# ProProject__3_0___2023-10-16.net
KiCad netlist of a schematic drawn in EasyEDA Pro
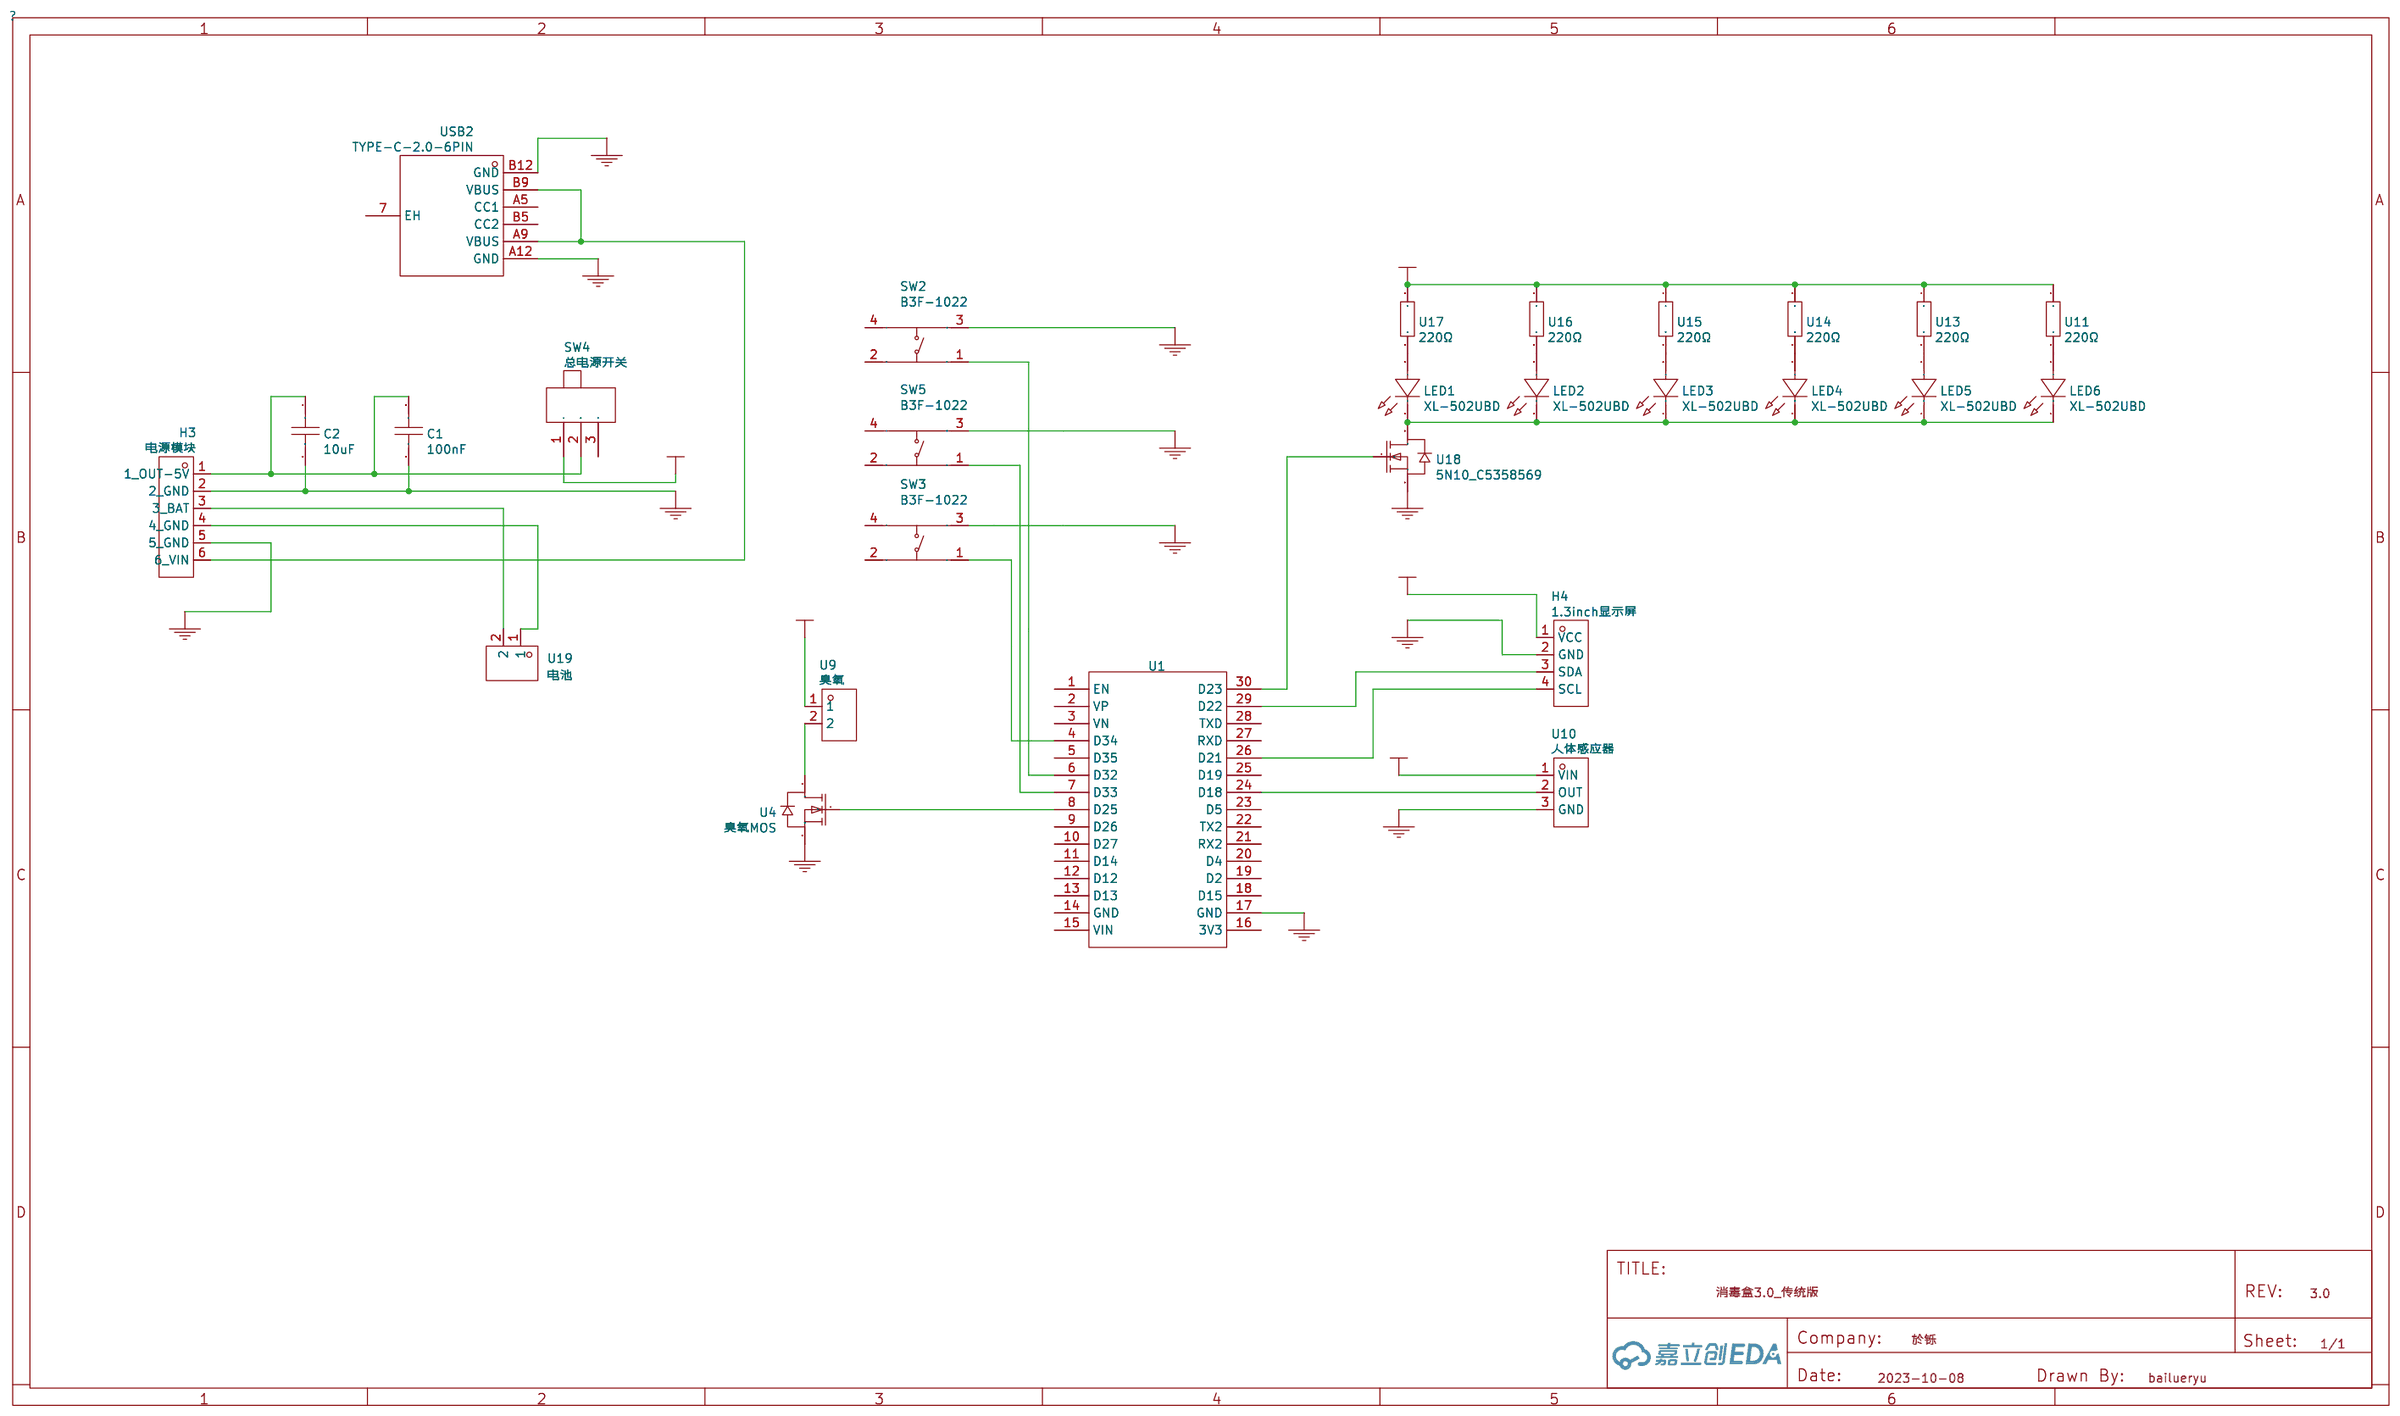
[diagram p0: schematic sheet]

(export (version "E")
  (design (tool "Eeschema 10.0.6"))
  (components
    (comp (ref "C1")
      (value "100nF")
      (footprint "easyedapro:C0603")
      (fields
        (field (name "Manufacturer Part") "MC0603B104K500N8RH")
        (field (name "Manufacturer") "Sunway(信维通信)")
      )
      (libsource (lib "easyedapro") (part "100nF"))
    )
    (comp (ref "C2")
      (value "10uF")
      (footprint "easyedapro:C0603")
      (fields (field (name "Manufacturer") "SAMSUNG(三星)"))
      (libsource (lib "easyedapro") (part "10uF"))
    )
    (comp (ref "H3")
      (value "电源模块")
      (footprint "easyedapro:HDR-TH_6P-P2.54-V-M")
      (fields (field (name "Manufacturer Part") "PZ254V-11-06P") (field (name "Manufacturer") "XFCN(兴飞)"))
      (libsource (lib "easyedapro") (part "电源模块"))
    )
    (comp (ref "H4")
      (value "1.3inch显示屏")
      (footprint "easyedapro:HDR-TH_4P-P2.54-V-M")
      (fields
        (field (name "Manufacturer Part") "KH-2.54PH180-1X4P-L11.5")
        (field (name "Manufacturer") "kinghelm(金航标)")
      )
      (libsource (lib "easyedapro") (part "1.3inch显示屏"))
    )
    (comp (ref "LED1")
      (value "XL-502UBD")
      (footprint "easyedapro:LED-TH_BD5.9-P2.54-RD_BLUE")
      (fields (field (name "Manufacturer") "XINGLIGHT(成兴光)"))
      (libsource (lib "easyedapro") (part "XL-502UBD"))
    )
    (comp (ref "LED2")
      (value "XL-502UBD")
      (footprint "easyedapro:LED-TH_BD5.9-P2.54-RD_BLUE")
      (fields (field (name "Manufacturer") "XINGLIGHT(成兴光)"))
      (libsource (lib "easyedapro") (part "XL-502UBD"))
    )
    (comp (ref "LED3")
      (value "XL-502UBD")
      (footprint "easyedapro:LED-TH_BD5.9-P2.54-RD_BLUE")
      (fields (field (name "Manufacturer") "XINGLIGHT(成兴光)"))
      (libsource (lib "easyedapro") (part "XL-502UBD"))
    )
    (comp (ref "LED4")
      (value "XL-502UBD")
      (footprint "easyedapro:LED-TH_BD5.9-P2.54-RD_BLUE")
      (fields (field (name "Manufacturer") "XINGLIGHT(成兴光)"))
      (libsource (lib "easyedapro") (part "XL-502UBD"))
    )
    (comp (ref "LED5")
      (value "XL-502UBD")
      (footprint "easyedapro:LED-TH_BD5.9-P2.54-RD_BLUE")
      (fields (field (name "Manufacturer") "XINGLIGHT(成兴光)"))
      (libsource (lib "easyedapro") (part "XL-502UBD"))
    )
    (comp (ref "LED6")
      (value "XL-502UBD")
      (footprint "easyedapro:LED-TH_BD5.9-P2.54-RD_BLUE")
      (fields (field (name "Manufacturer") "XINGLIGHT(成兴光)"))
      (libsource (lib "easyedapro") (part "XL-502UBD"))
    )
    (comp (ref "SW2")
      (value "B3F-1022")
      (footprint "easyedapro:SW-TH_4P-L6.0-W6.0-P4.50-LS6.5")
      (fields (field (name "Manufacturer") "OMRON(欧姆龙)"))
      (libsource (lib "easyedapro") (part "B3F-1022"))
    )
    (comp (ref "SW3")
      (value "B3F-1022")
      (footprint "easyedapro:SW-TH_4P-L6.0-W6.0-P4.50-LS6.5")
      (fields (field (name "Manufacturer") "OMRON(欧姆龙)"))
      (libsource (lib "easyedapro") (part "B3F-1022"))
    )
    (comp (ref "SW4")
      (value "总电源开关")
      (footprint "easyedapro:SW-TH_MK-12D18-G040")
      (fields (field (name "Manufacturer Part") "MK-12D18-G020") (field (name "Manufacturer") "G-Switch(品赞)"))
      (libsource (lib "easyedapro") (part "总电源开关"))
    )
    (comp (ref "SW5")
      (value "B3F-1022")
      (footprint "easyedapro:SW-TH_4P-L6.0-W6.0-P4.50-LS6.5")
      (fields (field (name "Manufacturer") "OMRON(欧姆龙)"))
      (libsource (lib "easyedapro") (part "B3F-1022"))
    )
    (comp (ref "U1")
      (value "NO")
      (footprint "easyedapro:ESP-WROOM-32")
      (libsource (lib "easyedapro") (part "NO"))
    )
    (comp (ref "U4")
      (value "臭氧MOS")
      (footprint "easyedapro:SOT-23-3_L2.9-W1.3-P1.90-LS2.4-BR")
      (fields (field (name "Manufacturer Part") "5N10") (field (name "Manufacturer") "GOODWORK(固得沃克)"))
      (libsource (lib "easyedapro") (part "臭氧MOS"))
    )
    (comp (ref "U9")
      (value "臭氧")
      (footprint "easyedapro:HDR-TH_2P-P2.00-V-M")
      (fields
        (field (name "Manufacturer Part") "DS1025-01-1x2P8BV1-B")
        (field (name "Manufacturer") "CONNFLY")
      )
      (libsource (lib "easyedapro") (part "臭氧"))
    )
    (comp (ref "U10")
      (value "人体感应器")
      (footprint "easyedapro:HDR-TH_3P-P2.00-V-M")
      (fields
        (field (name "Manufacturer Part") "DS1025-01-1x3P8BV1-B")
        (field (name "Manufacturer") "CONNFLY")
      )
      (libsource (lib "easyedapro") (part "人体感应器"))
    )
    (comp (ref "U11")
      (value "220Ω")
      (footprint "easyedapro:RES-TH_BD2.3-L3.7-P7.70-D0.9")
      (fields (field (name "Manufacturer Part") "MF1/8W-220Ω±1%-ST52") (field (name "Manufacturer") "VO(翔胜)"))
      (libsource (lib "easyedapro") (part "220Ω"))
    )
    (comp (ref "U13")
      (value "220Ω")
      (footprint "easyedapro:RES-TH_BD2.3-L3.7-P7.70-D0.9")
      (fields (field (name "Manufacturer Part") "MF1/8W-220Ω±1%-ST52") (field (name "Manufacturer") "VO(翔胜)"))
      (libsource (lib "easyedapro") (part "220Ω"))
    )
    (comp (ref "U14")
      (value "220Ω")
      (footprint "easyedapro:RES-TH_BD2.3-L3.7-P7.70-D0.9")
      (fields (field (name "Manufacturer Part") "MF1/8W-220Ω±1%-ST52") (field (name "Manufacturer") "VO(翔胜)"))
      (libsource (lib "easyedapro") (part "220Ω"))
    )
    (comp (ref "U15")
      (value "220Ω")
      (footprint "easyedapro:RES-TH_BD2.3-L3.7-P7.70-D0.9")
      (fields (field (name "Manufacturer Part") "MF1/8W-220Ω±1%-ST52") (field (name "Manufacturer") "VO(翔胜)"))
      (libsource (lib "easyedapro") (part "220Ω"))
    )
    (comp (ref "U16")
      (value "220Ω")
      (footprint "easyedapro:RES-TH_BD2.3-L3.7-P7.70-D0.9")
      (fields (field (name "Manufacturer Part") "MF1/8W-220Ω±1%-ST52") (field (name "Manufacturer") "VO(翔胜)"))
      (libsource (lib "easyedapro") (part "220Ω"))
    )
    (comp (ref "U17")
      (value "220Ω")
      (footprint "easyedapro:RES-TH_BD2.3-L3.7-P7.70-D0.9")
      (fields (field (name "Manufacturer Part") "MF1/8W-220Ω±1%-ST52") (field (name "Manufacturer") "VO(翔胜)"))
      (libsource (lib "easyedapro") (part "220Ω"))
    )
    (comp (ref "U18")
      (value "5N10_C5358569")
      (footprint "easyedapro:SOT-23-3_L2.9-W1.3-P1.90-LS2.4-BR")
      (fields (field (name "Manufacturer Part") "5N10") (field (name "Manufacturer") "GOODWORK(固得沃克)"))
      (libsource (lib "easyedapro") (part "5N10_C5358569"))
    )
    (comp (ref "U19")
      (value "电池")
      (footprint "easyedapro:HDR-TH_2P-P2.00-V-M")
      (fields
        (field (name "Manufacturer Part") "DS1025-01-1x2P8BV1-B")
        (field (name "Manufacturer") "CONNFLY")
      )
      (libsource (lib "easyedapro") (part "臭氧"))
    )
    (comp (ref "USB2")
      (value "TYPE-C-2.0-6PIN")
      (footprint "easyedapro:TYPE-C-SMD_TYPE-C-6P-2")
      (fields (field (name "Manufacturer Part") "Type-C-2.0-6Pin") (field (name "Manufacturer") "CIKI(皓富)"))
      (libsource (lib "easyedapro") (part "TYPE-C-2.0-6PIN"))
    )
  )
  (nets
    (net (code "1") (name "GND") (class "Default")
      (node (ref "C1") (pin "1") (pinfunction "1_1") (pintype "input"))
      (node (ref "C2") (pin "2") (pinfunction "2_2") (pintype "input"))
      (node (ref "H3") (pin "2") (pinfunction "2_GND_2") (pintype "input"))
      (node (ref "H3") (pin "5") (pinfunction "5_GND_5") (pintype "input"))
      (node (ref "H4") (pin "2") (pinfunction "GND_2") (pintype "input"))
      (node (ref "SW2") (pin "3") (pinfunction "3_3") (pintype "input"))
      (node (ref "SW3") (pin "3") (pinfunction "3_3") (pintype "input"))
      (node (ref "SW5") (pin "3") (pinfunction "3_3") (pintype "input"))
      (node (ref "U1") (pin "17") (pinfunction "GND_17") (pintype "input"))
      (node (ref "U10") (pin "3") (pinfunction "GND_3") (pintype "input"))
      (node (ref "U18") (pin "2") (pinfunction "S_2") (pintype "input"))
      (node (ref "U4") (pin "2") (pinfunction "S_2") (pintype "input"))
      (node (ref "USB2") (pin "A12") (pinfunction "GND_A12") (pintype "input"))
      (node (ref "USB2") (pin "B12") (pinfunction "GND_B12") (pintype "input"))
    )
    (net (code "2") (name "Net-(H3-1_OUT-5V)") (class "Default")
      (node (ref "C1") (pin "2") (pinfunction "2_2") (pintype "input"))
      (node (ref "C2") (pin "1") (pinfunction "1_1") (pintype "input"))
      (node (ref "H3") (pin "1") (pinfunction "1_OUT-5V_1") (pintype "input"))
      (node (ref "SW4") (pin "2") (pinfunction "2_2") (pintype "input"))
    )
    (net (code "3") (name "Net-(H3-3_BAT)") (class "Default")
      (node (ref "H3") (pin "3") (pinfunction "3_BAT_3") (pintype "input"))
      (node (ref "U19") (pin "2") (pinfunction "2_2") (pintype "input"))
    )
    (net (code "4") (name "Net-(H3-4_GND)") (class "Default")
      (node (ref "H3") (pin "4") (pinfunction "4_GND_4") (pintype "input"))
      (node (ref "U19") (pin "1") (pinfunction "1_1") (pintype "input"))
    )
    (net (code "5") (name "Net-(H3-6_VIN)") (class "Default")
      (node (ref "H3") (pin "6") (pinfunction "6_VIN_6") (pintype "input"))
      (node (ref "USB2") (pin "A9") (pinfunction "VBUS_A9") (pintype "input"))
      (node (ref "USB2") (pin "B9") (pinfunction "VBUS_B9") (pintype "input"))
    )
    (net (code "6") (name "Net-(H4-SCL)") (class "Default")
      (node (ref "H4") (pin "4") (pinfunction "SCL_4") (pintype "input"))
      (node (ref "U1") (pin "26") (pinfunction "D21_26") (pintype "input"))
    )
    (net (code "7") (name "Net-(H4-SDA)") (class "Default")
      (node (ref "H4") (pin "3") (pinfunction "SDA_3") (pintype "input"))
      (node (ref "U1") (pin "29") (pinfunction "D22_29") (pintype "input"))
    )
    (net (code "8") (name "Net-(LED1-A)") (class "Default")
      (node (ref "LED1") (pin "2") (pinfunction "A_2") (pintype "input"))
      (node (ref "U17") (pin "2") (pinfunction "2_2") (pintype "input"))
    )
    (net (code "9") (name "Net-(LED1-K)") (class "Default")
      (node (ref "LED1") (pin "1") (pinfunction "K_1") (pintype "input"))
      (node (ref "LED2") (pin "1") (pinfunction "K_1") (pintype "input"))
      (node (ref "LED3") (pin "1") (pinfunction "K_1") (pintype "input"))
      (node (ref "LED4") (pin "1") (pinfunction "K_1") (pintype "input"))
      (node (ref "LED5") (pin "1") (pinfunction "K_1") (pintype "input"))
      (node (ref "LED6") (pin "1") (pinfunction "K_1") (pintype "input"))
      (node (ref "U18") (pin "3") (pinfunction "D_3") (pintype "input"))
    )
    (net (code "10") (name "Net-(LED2-A)") (class "Default")
      (node (ref "LED2") (pin "2") (pinfunction "A_2") (pintype "input"))
      (node (ref "U16") (pin "2") (pinfunction "2_2") (pintype "input"))
    )
    (net (code "11") (name "Net-(LED3-A)") (class "Default")
      (node (ref "LED3") (pin "2") (pinfunction "A_2") (pintype "input"))
      (node (ref "U15") (pin "2") (pinfunction "2_2") (pintype "input"))
    )
    (net (code "12") (name "Net-(LED4-A)") (class "Default")
      (node (ref "LED4") (pin "2") (pinfunction "A_2") (pintype "input"))
      (node (ref "U14") (pin "2") (pinfunction "2_2") (pintype "input"))
    )
    (net (code "13") (name "Net-(LED5-A)") (class "Default")
      (node (ref "LED5") (pin "2") (pinfunction "A_2") (pintype "input"))
      (node (ref "U13") (pin "2") (pinfunction "2_2") (pintype "input"))
    )
    (net (code "14") (name "Net-(LED6-A)") (class "Default")
      (node (ref "LED6") (pin "2") (pinfunction "A_2") (pintype "input"))
      (node (ref "U11") (pin "2") (pinfunction "2_2") (pintype "input"))
    )
    (net (code "15") (name "Net-(U1-D18)") (class "Default")
      (node (ref "U1") (pin "24") (pinfunction "D18_24") (pintype "input"))
      (node (ref "U10") (pin "2") (pinfunction "OUT_2") (pintype "input"))
    )
    (net (code "16") (name "Net-(U1-D23)") (class "Default")
      (node (ref "U1") (pin "30") (pinfunction "D23_30") (pintype "input"))
      (node (ref "U18") (pin "1") (pinfunction "G_1") (pintype "input"))
    )
    (net (code "17") (name "Net-(U1-D25)") (class "Default")
      (node (ref "U1") (pin "8") (pinfunction "D25_8") (pintype "input"))
      (node (ref "U4") (pin "1") (pinfunction "G_1") (pintype "input"))
    )
    (net (code "18") (name "Net-(U1-D32)") (class "Default")
      (node (ref "SW2") (pin "1") (pinfunction "1_1") (pintype "input"))
      (node (ref "U1") (pin "6") (pinfunction "D32_6") (pintype "input"))
    )
    (net (code "19") (name "Net-(U1-D33)") (class "Default")
      (node (ref "SW5") (pin "1") (pinfunction "1_1") (pintype "input"))
      (node (ref "U1") (pin "7") (pinfunction "D33_7") (pintype "input"))
    )
    (net (code "20") (name "Net-(U1-D34)") (class "Default")
      (node (ref "SW3") (pin "1") (pinfunction "1_1") (pintype "input"))
      (node (ref "U1") (pin "4") (pinfunction "D34_4") (pintype "input"))
    )
    (net (code "21") (name "Net-(U4-D)") (class "Default")
      (node (ref "U4") (pin "3") (pinfunction "D_3") (pintype "input"))
      (node (ref "U9") (pin "2") (pinfunction "2_2") (pintype "input"))
    )
    (net (code "22") (name "VCC") (class "Default")
      (node (ref "H4") (pin "1") (pinfunction "VCC_1") (pintype "input"))
      (node (ref "SW4") (pin "1") (pinfunction "1_1") (pintype "input"))
      (node (ref "U10") (pin "1") (pinfunction "VIN_1") (pintype "input"))
      (node (ref "U11") (pin "1") (pinfunction "1_1") (pintype "input"))
      (node (ref "U13") (pin "1") (pinfunction "1_1") (pintype "input"))
      (node (ref "U14") (pin "1") (pinfunction "1_1") (pintype "input"))
      (node (ref "U15") (pin "1") (pinfunction "1_1") (pintype "input"))
      (node (ref "U16") (pin "1") (pinfunction "1_1") (pintype "input"))
      (node (ref "U17") (pin "1") (pinfunction "1_1") (pintype "input"))
      (node (ref "U9") (pin "1") (pinfunction "1_1") (pintype "input"))
    )
    (net (code "23") (name "unconnected-(SW2-Pad2)") (class "Default")
      (node (ref "SW2") (pin "2") (pinfunction "2_2") (pintype "input"))
    )
    (net (code "24") (name "unconnected-(SW2-Pad4)") (class "Default")
      (node (ref "SW2") (pin "4") (pinfunction "4_4") (pintype "input"))
    )
    (net (code "25") (name "unconnected-(SW3-Pad2)") (class "Default")
      (node (ref "SW3") (pin "2") (pinfunction "2_2") (pintype "input"))
    )
    (net (code "26") (name "unconnected-(SW3-Pad4)") (class "Default")
      (node (ref "SW3") (pin "4") (pinfunction "4_4") (pintype "input"))
    )
    (net (code "27") (name "unconnected-(SW4-Pad3)") (class "Default")
      (node (ref "SW4") (pin "3") (pinfunction "3_3") (pintype "input"))
    )
    (net (code "28") (name "unconnected-(SW5-Pad2)") (class "Default")
      (node (ref "SW5") (pin "2") (pinfunction "2_2") (pintype "input"))
    )
    (net (code "29") (name "unconnected-(SW5-Pad4)") (class "Default")
      (node (ref "SW5") (pin "4") (pinfunction "4_4") (pintype "input"))
    )
    (net (code "30") (name "unconnected-(U1-3V3-Pad16)") (class "Default")
      (node (ref "U1") (pin "16") (pinfunction "3V3_16") (pintype "input"))
    )
    (net (code "31") (name "unconnected-(U1-D2-Pad19)") (class "Default")
      (node (ref "U1") (pin "19") (pinfunction "D2_19") (pintype "input"))
    )
    (net (code "32") (name "unconnected-(U1-D4-Pad20)") (class "Default")
      (node (ref "U1") (pin "20") (pinfunction "D4_20") (pintype "input"))
    )
    (net (code "33") (name "unconnected-(U1-D5-Pad23)") (class "Default")
      (node (ref "U1") (pin "23") (pinfunction "D5_23") (pintype "input"))
    )
    (net (code "34") (name "unconnected-(U1-D12-Pad12)") (class "Default")
      (node (ref "U1") (pin "12") (pinfunction "D12_12") (pintype "input"))
    )
    (net (code "35") (name "unconnected-(U1-D13-Pad13)") (class "Default")
      (node (ref "U1") (pin "13") (pinfunction "D13_13") (pintype "input"))
    )
    (net (code "36") (name "unconnected-(U1-D14-Pad11)") (class "Default")
      (node (ref "U1") (pin "11") (pinfunction "D14_11") (pintype "input"))
    )
    (net (code "37") (name "unconnected-(U1-D15-Pad18)") (class "Default")
      (node (ref "U1") (pin "18") (pinfunction "D15_18") (pintype "input"))
    )
    (net (code "38") (name "unconnected-(U1-D19-Pad25)") (class "Default")
      (node (ref "U1") (pin "25") (pinfunction "D19_25") (pintype "input"))
    )
    (net (code "39") (name "unconnected-(U1-D26-Pad9)") (class "Default")
      (node (ref "U1") (pin "9") (pinfunction "D26_9") (pintype "input"))
    )
    (net (code "40") (name "unconnected-(U1-D27-Pad10)") (class "Default")
      (node (ref "U1") (pin "10") (pinfunction "D27_10") (pintype "input"))
    )
    (net (code "41") (name "unconnected-(U1-D35-Pad5)") (class "Default")
      (node (ref "U1") (pin "5") (pinfunction "D35_5") (pintype "input"))
    )
    (net (code "42") (name "unconnected-(U1-EN-Pad1)") (class "Default")
      (node (ref "U1") (pin "1") (pinfunction "EN_1") (pintype "input"))
    )
    (net (code "43") (name "unconnected-(U1-GND-Pad14)") (class "Default")
      (node (ref "U1") (pin "14") (pinfunction "GND_14") (pintype "input"))
    )
    (net (code "44") (name "unconnected-(U1-RX2-Pad21)") (class "Default")
      (node (ref "U1") (pin "21") (pinfunction "RX2_21") (pintype "input"))
    )
    (net (code "45") (name "unconnected-(U1-RXD-Pad27)") (class "Default")
      (node (ref "U1") (pin "27") (pinfunction "RXD_27") (pintype "input"))
    )
    (net (code "46") (name "unconnected-(U1-TX2-Pad22)") (class "Default")
      (node (ref "U1") (pin "22") (pinfunction "TX2_22") (pintype "input"))
    )
    (net (code "47") (name "unconnected-(U1-TXD-Pad28)") (class "Default")
      (node (ref "U1") (pin "28") (pinfunction "TXD_28") (pintype "input"))
    )
    (net (code "48") (name "unconnected-(U1-VIN-Pad15)") (class "Default")
      (node (ref "U1") (pin "15") (pinfunction "VIN_15") (pintype "input"))
    )
    (net (code "49") (name "unconnected-(U1-VN-Pad3)") (class "Default")
      (node (ref "U1") (pin "3") (pinfunction "VN_3") (pintype "input"))
    )
    (net (code "50") (name "unconnected-(U1-VP-Pad2)") (class "Default")
      (node (ref "U1") (pin "2") (pinfunction "VP_2") (pintype "input"))
    )
    (net (code "51") (name "unconnected-(USB2-CC1-PadA5)") (class "Default")
      (node (ref "USB2") (pin "A5") (pinfunction "CC1_A5") (pintype "input"))
    )
    (net (code "52") (name "unconnected-(USB2-CC2-PadB5)") (class "Default")
      (node (ref "USB2") (pin "B5") (pinfunction "CC2_B5") (pintype "input"))
    )
    (net (code "53") (name "unconnected-(USB2-EH-Pad7)") (class "Default")
      (node (ref "USB2") (pin "7") (pinfunction "EH_7") (pintype "input"))
    )
  )
)
